# 7_ddr3_memory.net
KiCad netlist of a schematic drawn in Altium Designer
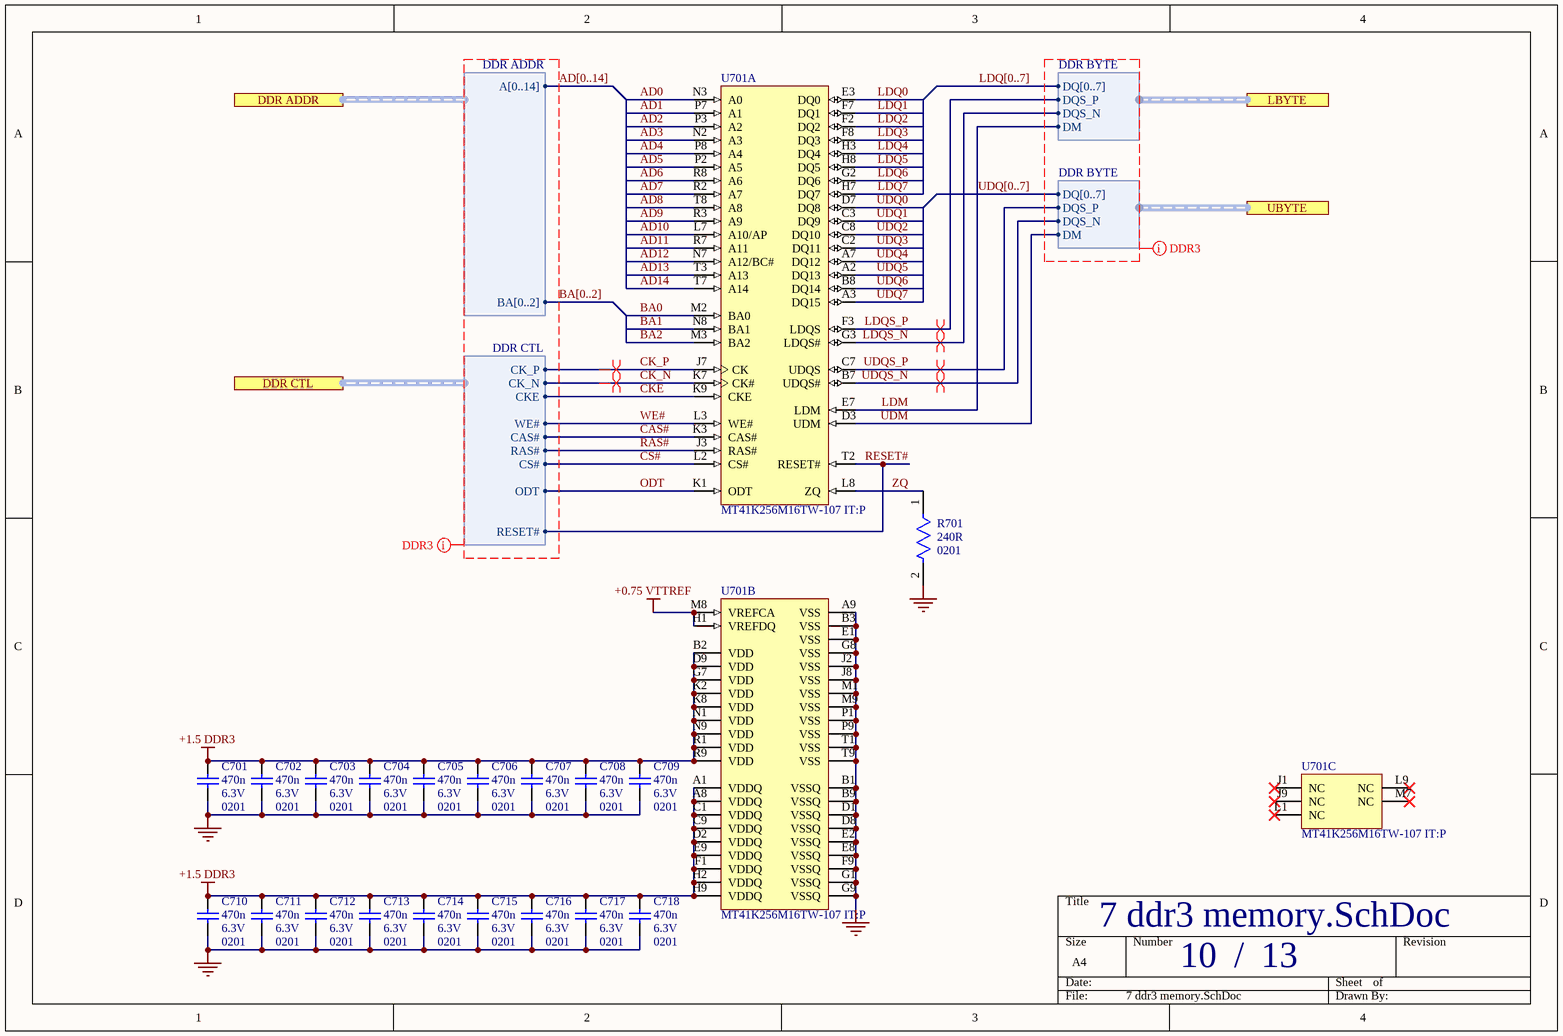
[diagram p0: 7 ddr3 memory.SchDoc]

(export (version "E")
  (design (tool "Eeschema 10.0.6"))
  (components
    (comp (ref "C701")
      (value "470n")
      (footprint "CAPC0603X33X15LL03T05")
      (fields
        (field (name "MANUFACTURER") "AVX Interconnect / Elco")
        (field (name "PART NUMBER") "02016D474KAT2A")
        (field (name "VOLTAGE RATING") "6.3V")
        (field (name "PACKAGE") "0201")
      )
      (libsource (lib "Altium Content Vault") (part "CAP"))
    )
    (comp (ref "C702")
      (value "470n")
      (footprint "CAPC0603X33X15LL03T05")
      (fields
        (field (name "MANUFACTURER") "AVX Interconnect / Elco")
        (field (name "PART NUMBER") "02016D474KAT2A")
        (field (name "VOLTAGE RATING") "6.3V")
        (field (name "PACKAGE") "0201")
      )
      (libsource (lib "Altium Content Vault") (part "CAP"))
    )
    (comp (ref "C703")
      (value "470n")
      (footprint "CAPC0603X33X15LL03T05")
      (fields
        (field (name "MANUFACTURER") "AVX Interconnect / Elco")
        (field (name "PART NUMBER") "02016D474KAT2A")
        (field (name "VOLTAGE RATING") "6.3V")
        (field (name "PACKAGE") "0201")
      )
      (libsource (lib "Altium Content Vault") (part "CAP"))
    )
    (comp (ref "C704")
      (value "470n")
      (footprint "CAPC0603X33X15LL03T05")
      (fields
        (field (name "MANUFACTURER") "AVX Interconnect / Elco")
        (field (name "PART NUMBER") "02016D474KAT2A")
        (field (name "VOLTAGE RATING") "6.3V")
        (field (name "PACKAGE") "0201")
      )
      (libsource (lib "Altium Content Vault") (part "CAP"))
    )
    (comp (ref "C705")
      (value "470n")
      (footprint "CAPC0603X33X15LL03T05")
      (fields
        (field (name "MANUFACTURER") "AVX Interconnect / Elco")
        (field (name "PART NUMBER") "02016D474KAT2A")
        (field (name "VOLTAGE RATING") "6.3V")
        (field (name "PACKAGE") "0201")
      )
      (libsource (lib "Altium Content Vault") (part "CAP"))
    )
    (comp (ref "C706")
      (value "470n")
      (footprint "CAPC0603X33X15LL03T05")
      (fields
        (field (name "MANUFACTURER") "AVX Interconnect / Elco")
        (field (name "PART NUMBER") "02016D474KAT2A")
        (field (name "VOLTAGE RATING") "6.3V")
        (field (name "PACKAGE") "0201")
      )
      (libsource (lib "Altium Content Vault") (part "CAP"))
    )
    (comp (ref "C707")
      (value "470n")
      (footprint "CAPC0603X33X15LL03T05")
      (fields
        (field (name "MANUFACTURER") "AVX Interconnect / Elco")
        (field (name "PART NUMBER") "02016D474KAT2A")
        (field (name "VOLTAGE RATING") "6.3V")
        (field (name "PACKAGE") "0201")
      )
      (libsource (lib "Altium Content Vault") (part "CAP"))
    )
    (comp (ref "C708")
      (value "470n")
      (footprint "CAPC0603X33X15LL03T05")
      (fields
        (field (name "MANUFACTURER") "AVX Interconnect / Elco")
        (field (name "PART NUMBER") "02016D474KAT2A")
        (field (name "VOLTAGE RATING") "6.3V")
        (field (name "PACKAGE") "0201")
      )
      (libsource (lib "Altium Content Vault") (part "CAP"))
    )
    (comp (ref "C709")
      (value "470n")
      (footprint "CAPC0603X33X15LL03T05")
      (fields
        (field (name "MANUFACTURER") "AVX Interconnect / Elco")
        (field (name "PART NUMBER") "02016D474KAT2A")
        (field (name "VOLTAGE RATING") "6.3V")
        (field (name "PACKAGE") "0201")
      )
      (libsource (lib "Altium Content Vault") (part "CAP"))
    )
    (comp (ref "C710")
      (value "470n")
      (footprint "CAPC0603X33X15LL03T05")
      (fields
        (field (name "MANUFACTURER") "AVX Interconnect / Elco")
        (field (name "PART NUMBER") "02016D474KAT2A")
        (field (name "VOLTAGE RATING") "6.3V")
        (field (name "PACKAGE") "0201")
      )
      (libsource (lib "Altium Content Vault") (part "CAP"))
    )
    (comp (ref "C711")
      (value "470n")
      (footprint "CAPC0603X33X15LL03T05")
      (fields
        (field (name "MANUFACTURER") "AVX Interconnect / Elco")
        (field (name "PART NUMBER") "02016D474KAT2A")
        (field (name "VOLTAGE RATING") "6.3V")
        (field (name "PACKAGE") "0201")
      )
      (libsource (lib "Altium Content Vault") (part "CAP"))
    )
    (comp (ref "C712")
      (value "470n")
      (footprint "CAPC0603X33X15LL03T05")
      (fields
        (field (name "MANUFACTURER") "AVX Interconnect / Elco")
        (field (name "PART NUMBER") "02016D474KAT2A")
        (field (name "VOLTAGE RATING") "6.3V")
        (field (name "PACKAGE") "0201")
      )
      (libsource (lib "Altium Content Vault") (part "CAP"))
    )
    (comp (ref "C713")
      (value "470n")
      (footprint "CAPC0603X33X15LL03T05")
      (fields
        (field (name "MANUFACTURER") "AVX Interconnect / Elco")
        (field (name "PART NUMBER") "02016D474KAT2A")
        (field (name "VOLTAGE RATING") "6.3V")
        (field (name "PACKAGE") "0201")
      )
      (libsource (lib "Altium Content Vault") (part "CAP"))
    )
    (comp (ref "C714")
      (value "470n")
      (footprint "CAPC0603X33X15LL03T05")
      (fields
        (field (name "MANUFACTURER") "AVX Interconnect / Elco")
        (field (name "PART NUMBER") "02016D474KAT2A")
        (field (name "VOLTAGE RATING") "6.3V")
        (field (name "PACKAGE") "0201")
      )
      (libsource (lib "Altium Content Vault") (part "CAP"))
    )
    (comp (ref "C715")
      (value "470n")
      (footprint "CAPC0603X33X15LL03T05")
      (fields
        (field (name "MANUFACTURER") "AVX Interconnect / Elco")
        (field (name "PART NUMBER") "02016D474KAT2A")
        (field (name "VOLTAGE RATING") "6.3V")
        (field (name "PACKAGE") "0201")
      )
      (libsource (lib "Altium Content Vault") (part "CAP"))
    )
    (comp (ref "C716")
      (value "470n")
      (footprint "CAPC0603X33X15LL03T05")
      (fields
        (field (name "MANUFACTURER") "AVX Interconnect / Elco")
        (field (name "PART NUMBER") "02016D474KAT2A")
        (field (name "VOLTAGE RATING") "6.3V")
        (field (name "PACKAGE") "0201")
      )
      (libsource (lib "Altium Content Vault") (part "CAP"))
    )
    (comp (ref "C717")
      (value "470n")
      (footprint "CAPC0603X33X15LL03T05")
      (fields
        (field (name "MANUFACTURER") "AVX Interconnect / Elco")
        (field (name "PART NUMBER") "02016D474KAT2A")
        (field (name "VOLTAGE RATING") "6.3V")
        (field (name "PACKAGE") "0201")
      )
      (libsource (lib "Altium Content Vault") (part "CAP"))
    )
    (comp (ref "C718")
      (value "470n")
      (footprint "CAPC0603X33X15LL03T05")
      (fields
        (field (name "MANUFACTURER") "AVX Interconnect / Elco")
        (field (name "PART NUMBER") "02016D474KAT2A")
        (field (name "VOLTAGE RATING") "6.3V")
        (field (name "PACKAGE") "0201")
      )
      (libsource (lib "Altium Content Vault") (part "CAP"))
    )
    (comp (ref "R701")
      (value "RMCF0201FG240R")
      (footprint "FP-RMCF0201-IPC_C")
      (description "240Ω ±1% 0.05W 0201 Thick Film Chip Resistor AEC-Q200 compliant")
      (fields
        (field (name "TOLERANCE") "1%")
        (field (name "CASE/PACKAGE") "0201")
        (field (name "RESISTANCE") "240R")
      )
      (libsource (lib "Altium Content Vault") (part "1029c3af85768c4190bb7ad29bc67b5"))
    )
    (comp (ref "U701")
      (value "MT41K256M16TW-107 IT:P")
      (footprint "MICT-TW-96")
      (description "Automotive DDR3L SDRAM, 4 GB, 933 MHz, 1.283 to 1.45 V, -40 to 95 degC, 96-Pin TFBGA, RoHS, Tray")
      (fields (field (name "MANUFACTURER") "Micron"))
      (libsource (lib "Altium Content Vault") (part "MICT-MT41K256M16-TW-96"))
    )
  )
  (nets
    (net (code "5") (name "+0.75 VTTREF") (class "Default")
      (node (ref "U701") (pin "H1") (pinfunction "VREFDQ_H1") (pintype "input"))
      (node (ref "U701") (pin "M8") (pinfunction "VREFCA_M8") (pintype "input"))
    )
    (net (code "6") (name "+1.5 DDR3") (class "Default")
      (node (ref "C701") (pin "1") (pinfunction "1_1") (pintype "passive"))
      (node (ref "C702") (pin "1") (pinfunction "1_1") (pintype "passive"))
      (node (ref "C703") (pin "1") (pinfunction "1_1") (pintype "passive"))
      (node (ref "C704") (pin "1") (pinfunction "1_1") (pintype "passive"))
      (node (ref "C705") (pin "1") (pinfunction "1_1") (pintype "passive"))
      (node (ref "C706") (pin "1") (pinfunction "1_1") (pintype "passive"))
      (node (ref "C707") (pin "1") (pinfunction "1_1") (pintype "passive"))
      (node (ref "C708") (pin "1") (pinfunction "1_1") (pintype "passive"))
      (node (ref "C709") (pin "1") (pinfunction "1_1") (pintype "passive"))
      (node (ref "C710") (pin "1") (pinfunction "1_1") (pintype "passive"))
      (node (ref "C711") (pin "1") (pinfunction "1_1") (pintype "passive"))
      (node (ref "C712") (pin "1") (pinfunction "1_1") (pintype "passive"))
      (node (ref "C713") (pin "1") (pinfunction "1_1") (pintype "passive"))
      (node (ref "C714") (pin "1") (pinfunction "1_1") (pintype "passive"))
      (node (ref "C715") (pin "1") (pinfunction "1_1") (pintype "passive"))
      (node (ref "C716") (pin "1") (pinfunction "1_1") (pintype "passive"))
      (node (ref "C717") (pin "1") (pinfunction "1_1") (pintype "passive"))
      (node (ref "C718") (pin "1") (pinfunction "1_1") (pintype "passive"))
      (node (ref "U701") (pin "A1") (pinfunction "VDDQ_A1") (pintype "power_in"))
      (node (ref "U701") (pin "A8") (pinfunction "VDDQ_A8") (pintype "power_in"))
      (node (ref "U701") (pin "B2") (pinfunction "VDD_B2") (pintype "power_in"))
      (node (ref "U701") (pin "C1") (pinfunction "VDDQ_C1") (pintype "power_in"))
      (node (ref "U701") (pin "C9") (pinfunction "VDDQ_C9") (pintype "power_in"))
      (node (ref "U701") (pin "D2") (pinfunction "VDDQ_D2") (pintype "power_in"))
      (node (ref "U701") (pin "D9") (pinfunction "VDD_D9") (pintype "power_in"))
      (node (ref "U701") (pin "E9") (pinfunction "VDDQ_E9") (pintype "power_in"))
      (node (ref "U701") (pin "F1") (pinfunction "VDDQ_F1") (pintype "power_in"))
      (node (ref "U701") (pin "G7") (pinfunction "VDD_G7") (pintype "power_in"))
      (node (ref "U701") (pin "H2") (pinfunction "VDDQ_H2") (pintype "power_in"))
      (node (ref "U701") (pin "H9") (pinfunction "VDDQ_H9") (pintype "power_in"))
      (node (ref "U701") (pin "K2") (pinfunction "VDD_K2") (pintype "power_in"))
      (node (ref "U701") (pin "K8") (pinfunction "VDD_K8") (pintype "power_in"))
      (node (ref "U701") (pin "N1") (pinfunction "VDD_N1") (pintype "power_in"))
      (node (ref "U701") (pin "N9") (pinfunction "VDD_N9") (pintype "power_in"))
      (node (ref "U701") (pin "R1") (pinfunction "VDD_R1") (pintype "power_in"))
      (node (ref "U701") (pin "R9") (pinfunction "VDD_R9") (pintype "power_in"))
    )
    (net (code "7") (name "/AD0") (class "Default")
      (node (ref "U701") (pin "N3") (pinfunction "A0_N3") (pintype "input"))
    )
    (net (code "8") (name "/AD1") (class "Default")
      (node (ref "U701") (pin "P7") (pinfunction "A1_P7") (pintype "input"))
    )
    (net (code "9") (name "/AD2") (class "Default")
      (node (ref "U701") (pin "P3") (pinfunction "A2_P3") (pintype "input"))
    )
    (net (code "10") (name "/AD3") (class "Default")
      (node (ref "U701") (pin "N2") (pinfunction "A3_N2") (pintype "input"))
    )
    (net (code "11") (name "/AD4") (class "Default")
      (node (ref "U701") (pin "P8") (pinfunction "A4_P8") (pintype "input"))
    )
    (net (code "12") (name "/AD5") (class "Default")
      (node (ref "U701") (pin "P2") (pinfunction "A5_P2") (pintype "input"))
    )
    (net (code "13") (name "/AD6") (class "Default")
      (node (ref "U701") (pin "R8") (pinfunction "A6_R8") (pintype "input"))
    )
    (net (code "14") (name "/AD7") (class "Default")
      (node (ref "U701") (pin "R2") (pinfunction "A7_R2") (pintype "input"))
    )
    (net (code "15") (name "/AD8") (class "Default")
      (node (ref "U701") (pin "T8") (pinfunction "A8_T8") (pintype "input"))
    )
    (net (code "16") (name "/AD9") (class "Default")
      (node (ref "U701") (pin "R3") (pinfunction "A9_R3") (pintype "input"))
    )
    (net (code "17") (name "/AD10") (class "Default")
      (node (ref "U701") (pin "L7") (pinfunction "A10/AP_L7") (pintype "input"))
    )
    (net (code "18") (name "/AD11") (class "Default")
      (node (ref "U701") (pin "R7") (pinfunction "A11_R7") (pintype "input"))
    )
    (net (code "19") (name "/AD12") (class "Default")
      (node (ref "U701") (pin "N7") (pinfunction "A12/BC#_N7") (pintype "input"))
    )
    (net (code "20") (name "/AD13") (class "Default")
      (node (ref "U701") (pin "T3") (pinfunction "A13_T3") (pintype "input"))
    )
    (net (code "21") (name "/AD14") (class "Default")
      (node (ref "U701") (pin "T7") (pinfunction "A14_T7") (pintype "input"))
    )
    (net (code "23") (name "/BA0") (class "Default")
      (node (ref "U701") (pin "M2") (pinfunction "BA0_M2") (pintype "input"))
    )
    (net (code "24") (name "/BA1") (class "Default")
      (node (ref "U701") (pin "N8") (pinfunction "BA1_N8") (pintype "input"))
    )
    (net (code "25") (name "/BA2") (class "Default")
      (node (ref "U701") (pin "M3") (pinfunction "BA2_M3") (pintype "input"))
    )
    (net (code "26") (name "/CAS#") (class "Default")
      (node (ref "U701") (pin "K3") (pinfunction "CAS#_K3") (pintype "input"))
    )
    (net (code "27") (name "/CKE") (class "Default")
      (node (ref "U701") (pin "K9") (pinfunction "CKE_K9") (pintype "input"))
    )
    (net (code "28") (name "/CK_N") (class "Default")
      (node (ref "U701") (pin "K7") (pinfunction "CK#_K7") (pintype "input"))
    )
    (net (code "29") (name "/CK_P") (class "Default")
      (node (ref "U701") (pin "J7") (pinfunction "CK_J7") (pintype "input"))
    )
    (net (code "30") (name "/CS#") (class "Default")
      (node (ref "U701") (pin "L2") (pinfunction "CS#_L2") (pintype "input"))
    )
    (net (code "32") (name "/LDM") (class "Default")
      (node (ref "U701") (pin "E7") (pinfunction "LDM_E7") (pintype "input"))
    )
    (net (code "33") (name "/LDQ0") (class "Default")
      (node (ref "U701") (pin "E3") (pinfunction "DQ0_E3") (pintype "bidirectional"))
    )
    (net (code "34") (name "/LDQ1") (class "Default")
      (node (ref "U701") (pin "F7") (pinfunction "DQ1_F7") (pintype "bidirectional"))
    )
    (net (code "35") (name "/LDQ2") (class "Default")
      (node (ref "U701") (pin "F2") (pinfunction "DQ2_F2") (pintype "bidirectional"))
    )
    (net (code "36") (name "/LDQ3") (class "Default")
      (node (ref "U701") (pin "F8") (pinfunction "DQ3_F8") (pintype "bidirectional"))
    )
    (net (code "37") (name "/LDQ4") (class "Default")
      (node (ref "U701") (pin "H3") (pinfunction "DQ4_H3") (pintype "bidirectional"))
    )
    (net (code "38") (name "/LDQ5") (class "Default")
      (node (ref "U701") (pin "H8") (pinfunction "DQ5_H8") (pintype "bidirectional"))
    )
    (net (code "39") (name "/LDQ6") (class "Default")
      (node (ref "U701") (pin "G2") (pinfunction "DQ6_G2") (pintype "bidirectional"))
    )
    (net (code "40") (name "/LDQ7") (class "Default")
      (node (ref "U701") (pin "H7") (pinfunction "DQ7_H7") (pintype "bidirectional"))
    )
    (net (code "41") (name "/LDQS_N") (class "Default")
      (node (ref "U701") (pin "G3") (pinfunction "LDQS#_G3") (pintype "bidirectional"))
    )
    (net (code "42") (name "/LDQS_P") (class "Default")
      (node (ref "U701") (pin "F3") (pinfunction "LDQS_F3") (pintype "bidirectional"))
    )
    (net (code "44") (name "/ODT") (class "Default")
      (node (ref "U701") (pin "K1") (pinfunction "ODT_K1") (pintype "input"))
    )
    (net (code "45") (name "/RAS#") (class "Default")
      (node (ref "U701") (pin "J3") (pinfunction "RAS#_J3") (pintype "input"))
    )
    (net (code "46") (name "/RESET#") (class "Default")
      (node (ref "U701") (pin "T2") (pinfunction "RESET#_T2") (pintype "input"))
    )
    (net (code "47") (name "/UDM") (class "Default")
      (node (ref "U701") (pin "D3") (pinfunction "UDM_D3") (pintype "input"))
    )
    (net (code "48") (name "/UDQ0") (class "Default")
      (node (ref "U701") (pin "D7") (pinfunction "DQ8_D7") (pintype "bidirectional"))
    )
    (net (code "49") (name "/UDQ1") (class "Default")
      (node (ref "U701") (pin "C3") (pinfunction "DQ9_C3") (pintype "bidirectional"))
    )
    (net (code "50") (name "/UDQ2") (class "Default")
      (node (ref "U701") (pin "C8") (pinfunction "DQ10_C8") (pintype "bidirectional"))
    )
    (net (code "51") (name "/UDQ3") (class "Default")
      (node (ref "U701") (pin "C2") (pinfunction "DQ11_C2") (pintype "bidirectional"))
    )
    (net (code "52") (name "/UDQ4") (class "Default")
      (node (ref "U701") (pin "A7") (pinfunction "DQ12_A7") (pintype "bidirectional"))
    )
    (net (code "53") (name "/UDQ5") (class "Default")
      (node (ref "U701") (pin "A2") (pinfunction "DQ13_A2") (pintype "bidirectional"))
    )
    (net (code "54") (name "/UDQ6") (class "Default")
      (node (ref "U701") (pin "B8") (pinfunction "DQ14_B8") (pintype "bidirectional"))
    )
    (net (code "55") (name "/UDQ7") (class "Default")
      (node (ref "U701") (pin "A3") (pinfunction "DQ15_A3") (pintype "bidirectional"))
    )
    (net (code "56") (name "/UDQS_N") (class "Default")
      (node (ref "U701") (pin "B7") (pinfunction "UDQS#_B7") (pintype "bidirectional"))
    )
    (net (code "57") (name "/UDQS_P") (class "Default")
      (node (ref "U701") (pin "C7") (pinfunction "UDQS_C7") (pintype "bidirectional"))
    )
    (net (code "59") (name "/WE#") (class "Default")
      (node (ref "U701") (pin "L3") (pinfunction "WE#_L3") (pintype "input"))
    )
    (net (code "60") (name "/ZQ") (class "Default")
      (node (ref "R701") (pin "1") (pinfunction "1_1") (pintype "passive"))
      (node (ref "U701") (pin "L8") (pinfunction "ZQ_L8") (pintype "input"))
    )
    (net (code "64") (name "GND") (class "Default")
      (node (ref "C701") (pin "2") (pinfunction "2_2") (pintype "passive"))
      (node (ref "C702") (pin "2") (pinfunction "2_2") (pintype "passive"))
      (node (ref "C703") (pin "2") (pinfunction "2_2") (pintype "passive"))
      (node (ref "C704") (pin "2") (pinfunction "2_2") (pintype "passive"))
      (node (ref "C705") (pin "2") (pinfunction "2_2") (pintype "passive"))
      (node (ref "C706") (pin "2") (pinfunction "2_2") (pintype "passive"))
      (node (ref "C707") (pin "2") (pinfunction "2_2") (pintype "passive"))
      (node (ref "C708") (pin "2") (pinfunction "2_2") (pintype "passive"))
      (node (ref "C709") (pin "2") (pinfunction "2_2") (pintype "passive"))
      (node (ref "C710") (pin "2") (pinfunction "2_2") (pintype "passive"))
      (node (ref "C711") (pin "2") (pinfunction "2_2") (pintype "passive"))
      (node (ref "C712") (pin "2") (pinfunction "2_2") (pintype "passive"))
      (node (ref "C713") (pin "2") (pinfunction "2_2") (pintype "passive"))
      (node (ref "C714") (pin "2") (pinfunction "2_2") (pintype "passive"))
      (node (ref "C715") (pin "2") (pinfunction "2_2") (pintype "passive"))
      (node (ref "C716") (pin "2") (pinfunction "2_2") (pintype "passive"))
      (node (ref "C717") (pin "2") (pinfunction "2_2") (pintype "passive"))
      (node (ref "C718") (pin "2") (pinfunction "2_2") (pintype "passive"))
      (node (ref "R701") (pin "2") (pinfunction "2_2") (pintype "passive"))
      (node (ref "U701") (pin "A9") (pinfunction "VSS_A9") (pintype "power_in"))
      (node (ref "U701") (pin "B1") (pinfunction "VSSQ_B1") (pintype "power_in"))
      (node (ref "U701") (pin "B3") (pinfunction "VSS_B3") (pintype "power_in"))
      (node (ref "U701") (pin "B9") (pinfunction "VSSQ_B9") (pintype "power_in"))
      (node (ref "U701") (pin "D1") (pinfunction "VSSQ_D1") (pintype "power_in"))
      (node (ref "U701") (pin "D8") (pinfunction "VSSQ_D8") (pintype "power_in"))
      (node (ref "U701") (pin "E1") (pinfunction "VSS_E1") (pintype "power_in"))
      (node (ref "U701") (pin "E2") (pinfunction "VSSQ_E2") (pintype "power_in"))
      (node (ref "U701") (pin "E8") (pinfunction "VSSQ_E8") (pintype "power_in"))
      (node (ref "U701") (pin "F9") (pinfunction "VSSQ_F9") (pintype "power_in"))
      (node (ref "U701") (pin "G1") (pinfunction "VSSQ_G1") (pintype "power_in"))
      (node (ref "U701") (pin "G8") (pinfunction "VSS_G8") (pintype "power_in"))
      (node (ref "U701") (pin "G9") (pinfunction "VSSQ_G9") (pintype "power_in"))
      (node (ref "U701") (pin "J2") (pinfunction "VSS_J2") (pintype "power_in"))
      (node (ref "U701") (pin "J8") (pinfunction "VSS_J8") (pintype "power_in"))
      (node (ref "U701") (pin "M1") (pinfunction "VSS_M1") (pintype "power_in"))
      (node (ref "U701") (pin "M9") (pinfunction "VSS_M9") (pintype "power_in"))
      (node (ref "U701") (pin "P1") (pinfunction "VSS_P1") (pintype "power_in"))
      (node (ref "U701") (pin "P9") (pinfunction "VSS_P9") (pintype "power_in"))
      (node (ref "U701") (pin "T1") (pinfunction "VSS_T1") (pintype "power_in"))
      (node (ref "U701") (pin "T9") (pinfunction "VSS_T9") (pintype "power_in"))
    )
    (net (code "65") (name "unconnected-(U701C-NC-PadJ1)") (class "Default")
      (node (ref "U701") (pin "J1") (pinfunction "NC_J1") (pintype "passive+no_connect"))
    )
    (net (code "66") (name "unconnected-(U701C-NC-PadJ9)") (class "Default")
      (node (ref "U701") (pin "J9") (pinfunction "NC_J9") (pintype "passive+no_connect"))
    )
    (net (code "67") (name "unconnected-(U701C-NC-PadL1)") (class "Default")
      (node (ref "U701") (pin "L1") (pinfunction "NC_L1") (pintype "passive+no_connect"))
    )
    (net (code "68") (name "unconnected-(U701C-NC-PadL9)") (class "Default")
      (node (ref "U701") (pin "L9") (pinfunction "NC_L9") (pintype "passive+no_connect"))
    )
    (net (code "69") (name "unconnected-(U701C-NC-PadM7)") (class "Default")
      (node (ref "U701") (pin "M7") (pinfunction "NC_M7") (pintype "passive+no_connect"))
    )
  )
)
